# ehomeLight.net
KiCad netlist of a schematic drawn in EAGLE
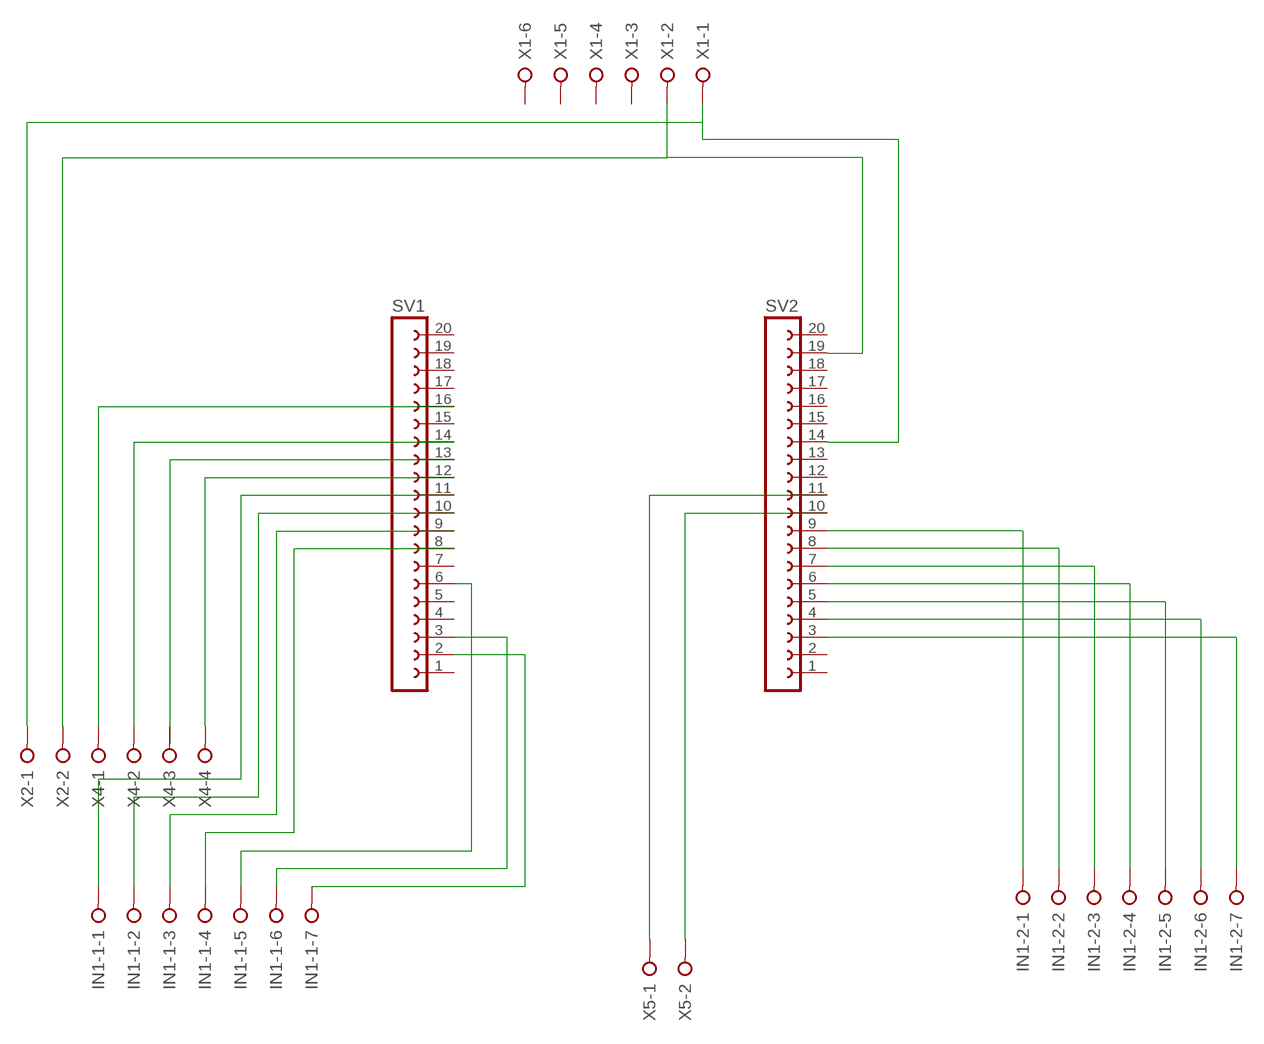
[diagram p0: schematic, sheet 1]

(export (version "E")
  (design (tool "Eeschema 10.0.6"))
  (components
    (comp (ref "IN1-1")
      (value "W237-07P")
      (footprint "eagle-import:W237-7P")
      (libsource (lib "eagle-import") (part "W237-07P"))
    )
    (comp (ref "IN1-2")
      (value "W237-07P")
      (footprint "eagle-import:W237-7P")
      (libsource (lib "eagle-import") (part "W237-07P"))
    )
    (comp (ref "SV1")
      (value "FE20-1")
      (footprint "eagle-import:FE20")
      (libsource (lib "eagle-import") (part "FE20-1"))
    )
    (comp (ref "SV2")
      (value "FE20-1")
      (footprint "eagle-import:FE20")
      (libsource (lib "eagle-import") (part "FE20-1"))
    )
    (comp (ref "X1")
      (value "W237-06P")
      (footprint "eagle-import:W237-6P")
      (libsource (lib "eagle-import") (part "W237-06P"))
    )
    (comp (ref "X2")
      (value "W237-02P")
      (footprint "eagle-import:W237-132")
      (libsource (lib "eagle-import") (part "W237-02P"))
    )
    (comp (ref "X4")
      (value "W237-04P")
      (footprint "eagle-import:W237-4P")
      (libsource (lib "eagle-import") (part "W237-04P"))
    )
    (comp (ref "X5")
      (value "W237-02P")
      (footprint "eagle-import:W237-132")
      (libsource (lib "eagle-import") (part "W237-02P"))
    )
  )
  (nets
    (net (code "1") (name "Net-(IN1-1A-KL)") (class "Default")
      (node (ref "IN1-1") (pin "1") (pinfunction "KL_1") (pintype "passive"))
      (node (ref "SV1") (pin "11") (pinfunction "11_11") (pintype "passive"))
    )
    (net (code "2") (name "Net-(IN1-1B-KL)") (class "Default")
      (node (ref "IN1-1") (pin "2") (pinfunction "KL_2") (pintype "passive"))
      (node (ref "SV1") (pin "10") (pinfunction "10_10") (pintype "passive"))
    )
    (net (code "3") (name "Net-(IN1-1C-KL)") (class "Default")
      (node (ref "IN1-1") (pin "3") (pinfunction "KL_3") (pintype "passive"))
      (node (ref "SV1") (pin "9") (pinfunction "9_9") (pintype "passive"))
    )
    (net (code "4") (name "Net-(IN1-1D-KL)") (class "Default")
      (node (ref "IN1-1") (pin "4") (pinfunction "KL_4") (pintype "passive"))
      (node (ref "SV1") (pin "8") (pinfunction "8_8") (pintype "passive"))
    )
    (net (code "5") (name "Net-(IN1-1E-KL)") (class "Default")
      (node (ref "IN1-1") (pin "5") (pinfunction "KL_5") (pintype "passive"))
      (node (ref "SV1") (pin "6") (pinfunction "6_6") (pintype "passive"))
    )
    (net (code "6") (name "Net-(IN1-1F-KL)") (class "Default")
      (node (ref "IN1-1") (pin "6") (pinfunction "KL_6") (pintype "passive"))
      (node (ref "SV1") (pin "3") (pinfunction "3_3") (pintype "passive"))
    )
    (net (code "7") (name "Net-(IN1-1G-KL)") (class "Default")
      (node (ref "IN1-1") (pin "7") (pinfunction "KL_7") (pintype "passive"))
      (node (ref "SV1") (pin "2") (pinfunction "2_2") (pintype "passive"))
    )
    (net (code "8") (name "Net-(IN1-2A-KL)") (class "Default")
      (node (ref "IN1-2") (pin "1") (pinfunction "KL_1") (pintype "passive"))
      (node (ref "SV2") (pin "9") (pinfunction "9_9") (pintype "passive"))
    )
    (net (code "9") (name "Net-(IN1-2B-KL)") (class "Default")
      (node (ref "IN1-2") (pin "2") (pinfunction "KL_2") (pintype "passive"))
      (node (ref "SV2") (pin "8") (pinfunction "8_8") (pintype "passive"))
    )
    (net (code "10") (name "Net-(IN1-2C-KL)") (class "Default")
      (node (ref "IN1-2") (pin "3") (pinfunction "KL_3") (pintype "passive"))
      (node (ref "SV2") (pin "7") (pinfunction "7_7") (pintype "passive"))
    )
    (net (code "11") (name "Net-(IN1-2D-KL)") (class "Default")
      (node (ref "IN1-2") (pin "4") (pinfunction "KL_4") (pintype "passive"))
      (node (ref "SV2") (pin "6") (pinfunction "6_6") (pintype "passive"))
    )
    (net (code "12") (name "Net-(IN1-2E-KL)") (class "Default")
      (node (ref "IN1-2") (pin "5") (pinfunction "KL_5") (pintype "passive"))
      (node (ref "SV2") (pin "5") (pinfunction "5_5") (pintype "passive"))
    )
    (net (code "13") (name "Net-(IN1-2F-KL)") (class "Default")
      (node (ref "IN1-2") (pin "6") (pinfunction "KL_6") (pintype "passive"))
      (node (ref "SV2") (pin "4") (pinfunction "4_4") (pintype "passive"))
    )
    (net (code "14") (name "Net-(IN1-2G-KL)") (class "Default")
      (node (ref "IN1-2") (pin "7") (pinfunction "KL_7") (pintype "passive"))
      (node (ref "SV2") (pin "3") (pinfunction "3_3") (pintype "passive"))
    )
    (net (code "15") (name "Net-(X1A-KL)") (class "Default")
      (node (ref "SV2") (pin "14") (pinfunction "14_14") (pintype "passive"))
      (node (ref "X1") (pin "1") (pinfunction "KL_1") (pintype "passive"))
      (node (ref "X2") (pin "1") (pinfunction "KL_1") (pintype "passive"))
    )
    (net (code "16") (name "Net-(X1B-KL)") (class "Default")
      (node (ref "SV2") (pin "19") (pinfunction "19_19") (pintype "passive"))
      (node (ref "X1") (pin "2") (pinfunction "KL_2") (pintype "passive"))
      (node (ref "X2") (pin "2") (pinfunction "KL_2") (pintype "passive"))
    )
    (net (code "17") (name "Net-(X4A-KL)") (class "Default")
      (node (ref "SV1") (pin "16") (pinfunction "16_16") (pintype "passive"))
      (node (ref "X4") (pin "1") (pinfunction "KL_1") (pintype "passive"))
    )
    (net (code "18") (name "Net-(X4B-KL)") (class "Default")
      (node (ref "SV1") (pin "14") (pinfunction "14_14") (pintype "passive"))
      (node (ref "X4") (pin "2") (pinfunction "KL_2") (pintype "passive"))
    )
    (net (code "19") (name "Net-(X4C-KL)") (class "Default")
      (node (ref "SV1") (pin "13") (pinfunction "13_13") (pintype "passive"))
      (node (ref "X4") (pin "3") (pinfunction "KL_3") (pintype "passive"))
    )
    (net (code "20") (name "Net-(X4D-KL)") (class "Default")
      (node (ref "SV1") (pin "12") (pinfunction "12_12") (pintype "passive"))
      (node (ref "X4") (pin "4") (pinfunction "KL_4") (pintype "passive"))
    )
    (net (code "21") (name "Net-(X5A-KL)") (class "Default")
      (node (ref "SV2") (pin "11") (pinfunction "11_11") (pintype "passive"))
      (node (ref "X5") (pin "1") (pinfunction "KL_1") (pintype "passive"))
    )
    (net (code "22") (name "Net-(X5B-KL)") (class "Default")
      (node (ref "SV2") (pin "10") (pinfunction "10_10") (pintype "passive"))
      (node (ref "X5") (pin "2") (pinfunction "KL_2") (pintype "passive"))
    )
    (net (code "23") (name "unconnected-(SV1-Pad1)") (class "Default")
      (node (ref "SV1") (pin "1") (pinfunction "1_1") (pintype "passive"))
    )
    (net (code "24") (name "unconnected-(SV1-Pad4)") (class "Default")
      (node (ref "SV1") (pin "4") (pinfunction "4_4") (pintype "passive"))
    )
    (net (code "25") (name "unconnected-(SV1-Pad5)") (class "Default")
      (node (ref "SV1") (pin "5") (pinfunction "5_5") (pintype "passive"))
    )
    (net (code "26") (name "unconnected-(SV1-Pad7)") (class "Default")
      (node (ref "SV1") (pin "7") (pinfunction "7_7") (pintype "passive"))
    )
    (net (code "27") (name "unconnected-(SV1-Pad15)") (class "Default")
      (node (ref "SV1") (pin "15") (pinfunction "15_15") (pintype "passive"))
    )
    (net (code "28") (name "unconnected-(SV1-Pad17)") (class "Default")
      (node (ref "SV1") (pin "17") (pinfunction "17_17") (pintype "passive"))
    )
    (net (code "29") (name "unconnected-(SV1-Pad18)") (class "Default")
      (node (ref "SV1") (pin "18") (pinfunction "18_18") (pintype "passive"))
    )
    (net (code "30") (name "unconnected-(SV1-Pad19)") (class "Default")
      (node (ref "SV1") (pin "19") (pinfunction "19_19") (pintype "passive"))
    )
    (net (code "31") (name "unconnected-(SV1-Pad20)") (class "Default")
      (node (ref "SV1") (pin "20") (pinfunction "20_20") (pintype "passive"))
    )
    (net (code "32") (name "unconnected-(SV2-Pad1)") (class "Default")
      (node (ref "SV2") (pin "1") (pinfunction "1_1") (pintype "passive"))
    )
    (net (code "33") (name "unconnected-(SV2-Pad2)") (class "Default")
      (node (ref "SV2") (pin "2") (pinfunction "2_2") (pintype "passive"))
    )
    (net (code "34") (name "unconnected-(SV2-Pad12)") (class "Default")
      (node (ref "SV2") (pin "12") (pinfunction "12_12") (pintype "passive"))
    )
    (net (code "35") (name "unconnected-(SV2-Pad13)") (class "Default")
      (node (ref "SV2") (pin "13") (pinfunction "13_13") (pintype "passive"))
    )
    (net (code "36") (name "unconnected-(SV2-Pad15)") (class "Default")
      (node (ref "SV2") (pin "15") (pinfunction "15_15") (pintype "passive"))
    )
    (net (code "37") (name "unconnected-(SV2-Pad16)") (class "Default")
      (node (ref "SV2") (pin "16") (pinfunction "16_16") (pintype "passive"))
    )
    (net (code "38") (name "unconnected-(SV2-Pad17)") (class "Default")
      (node (ref "SV2") (pin "17") (pinfunction "17_17") (pintype "passive"))
    )
    (net (code "39") (name "unconnected-(SV2-Pad18)") (class "Default")
      (node (ref "SV2") (pin "18") (pinfunction "18_18") (pintype "passive"))
    )
    (net (code "40") (name "unconnected-(SV2-Pad20)") (class "Default")
      (node (ref "SV2") (pin "20") (pinfunction "20_20") (pintype "passive"))
    )
    (net (code "41") (name "unconnected-(X1C-KL-Pad3)") (class "Default")
      (node (ref "X1") (pin "3") (pinfunction "KL_3") (pintype "passive"))
    )
    (net (code "42") (name "unconnected-(X1D-KL-Pad4)") (class "Default")
      (node (ref "X1") (pin "4") (pinfunction "KL_4") (pintype "passive"))
    )
    (net (code "43") (name "unconnected-(X1E-KL-Pad5)") (class "Default")
      (node (ref "X1") (pin "5") (pinfunction "KL_5") (pintype "passive"))
    )
    (net (code "44") (name "unconnected-(X1F-KL-Pad6)") (class "Default")
      (node (ref "X1") (pin "6") (pinfunction "KL_6") (pintype "passive"))
    )
  )
)
